# CanBus-8x-Schalter.net
KiCad netlist of a schematic drawn in EAGLE
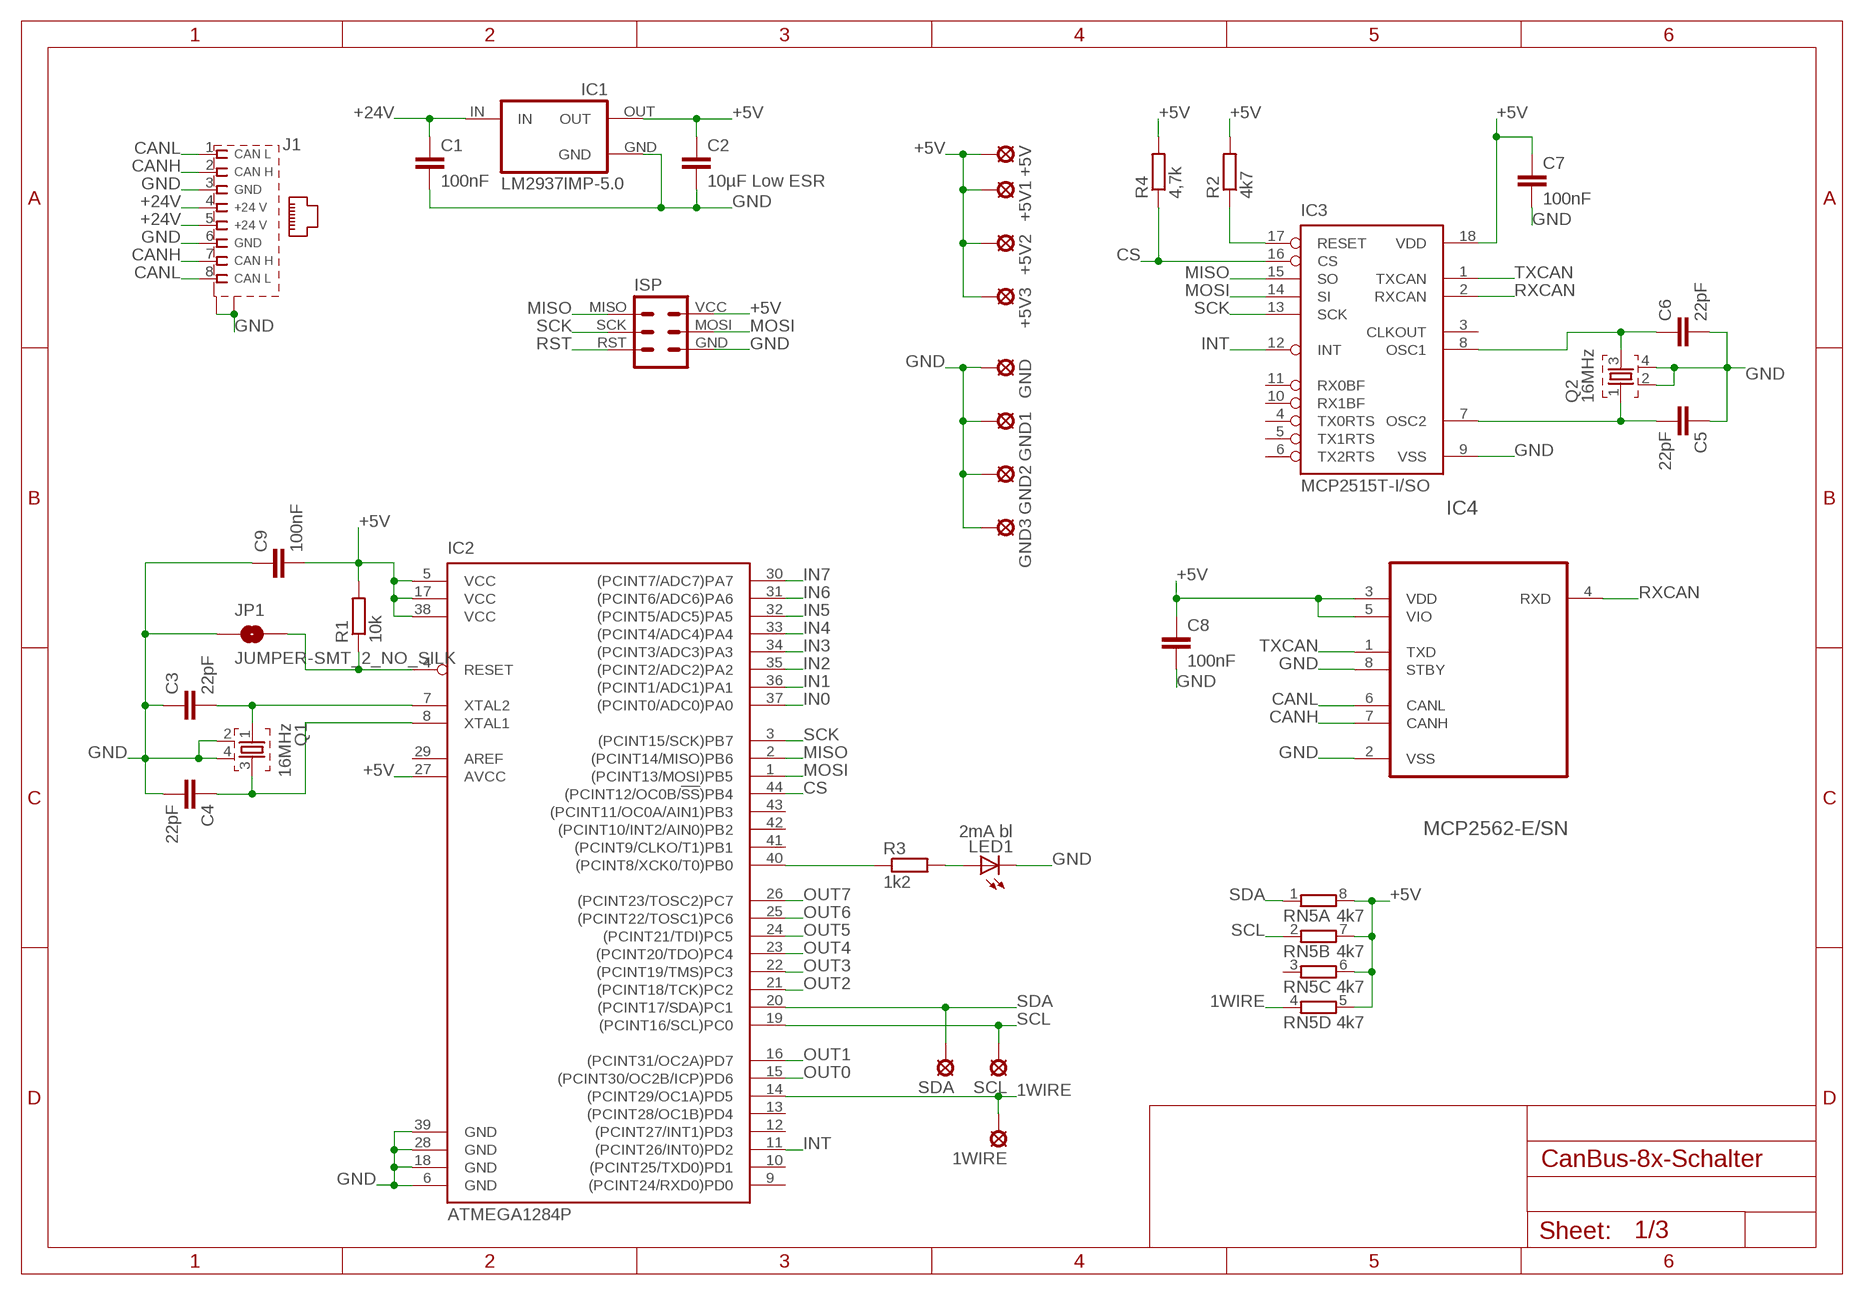
[diagram p0: schematic, sheet 1]
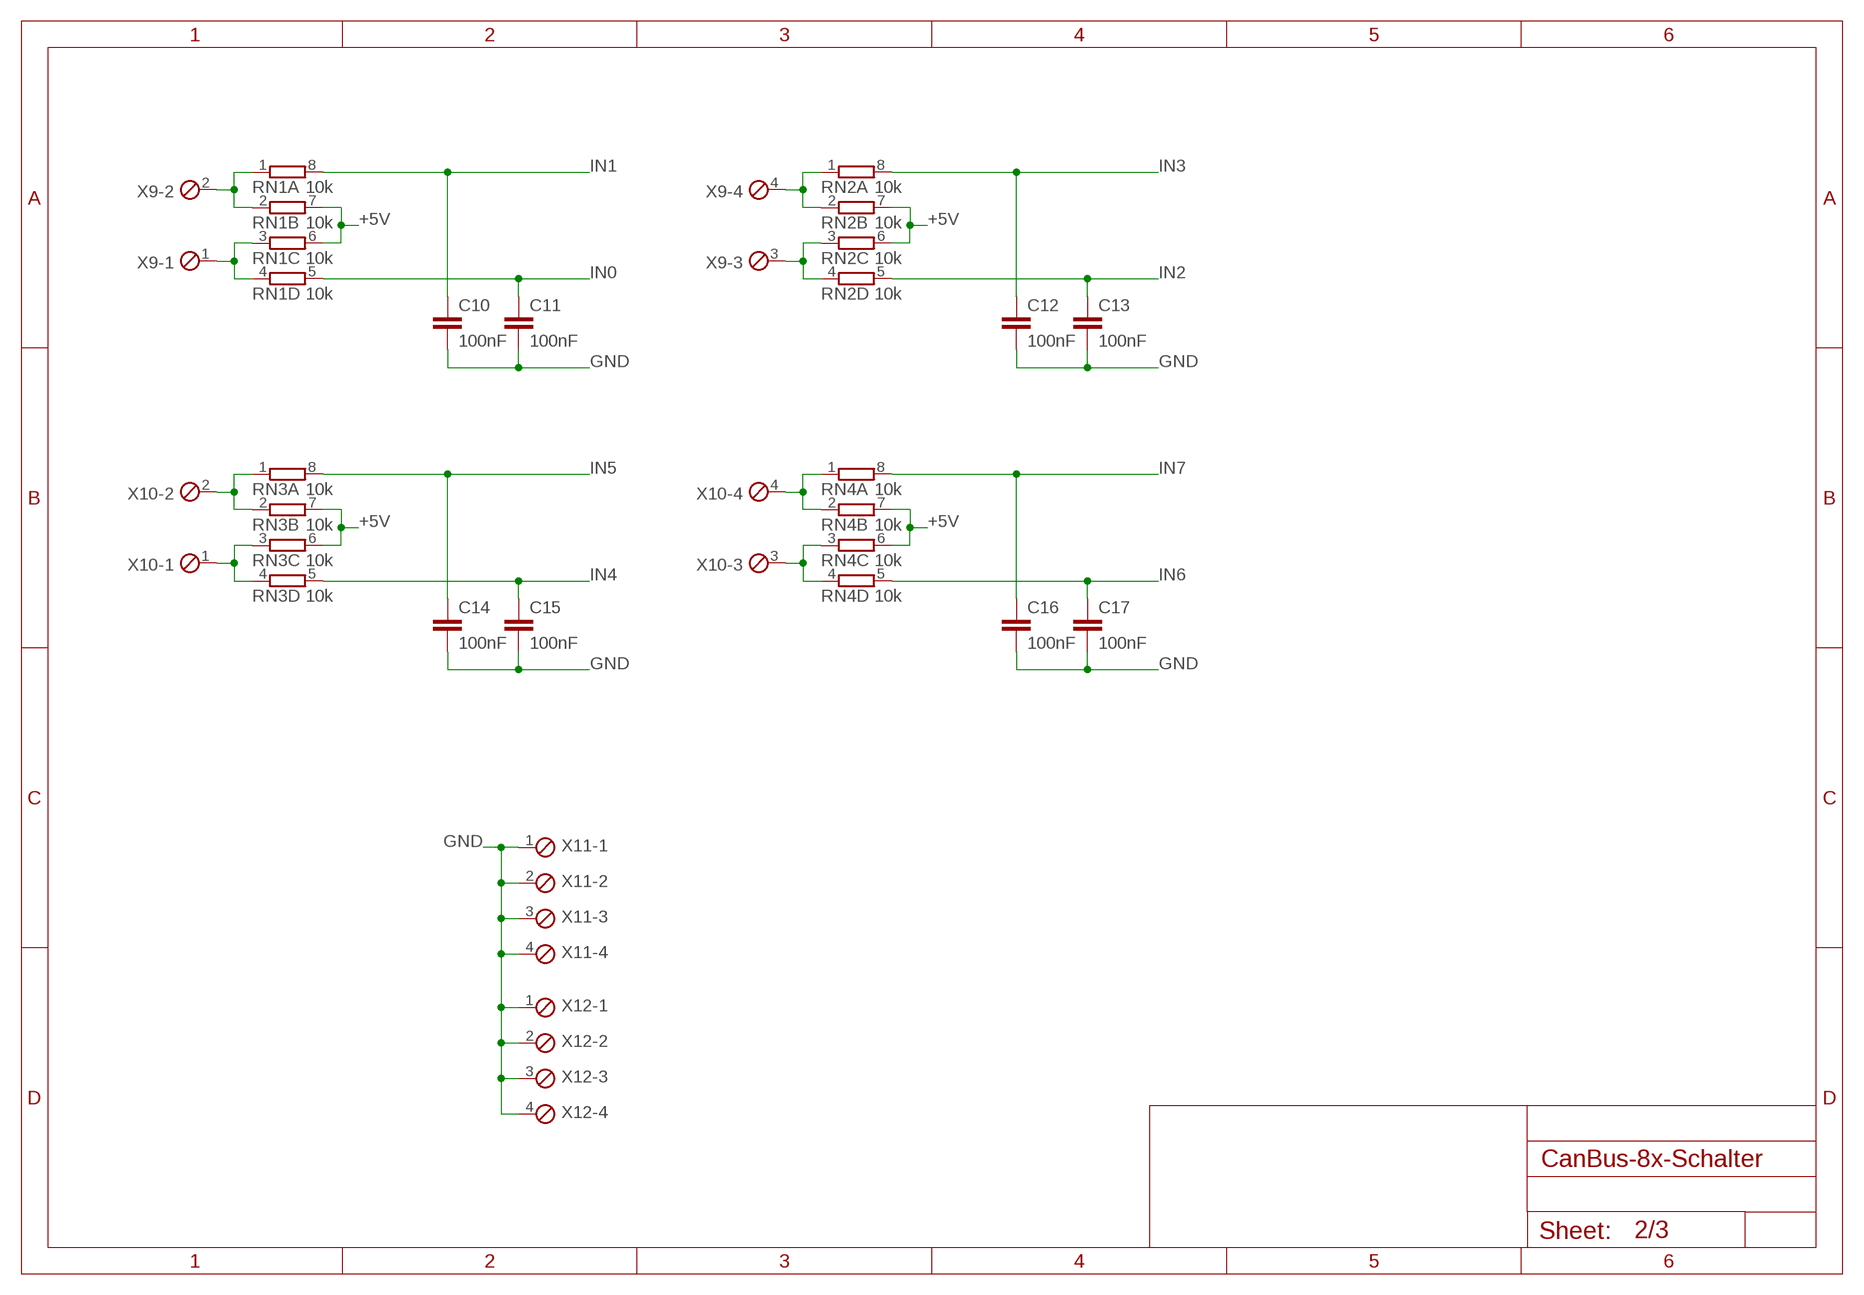
[diagram p1: schematic, sheet 2]
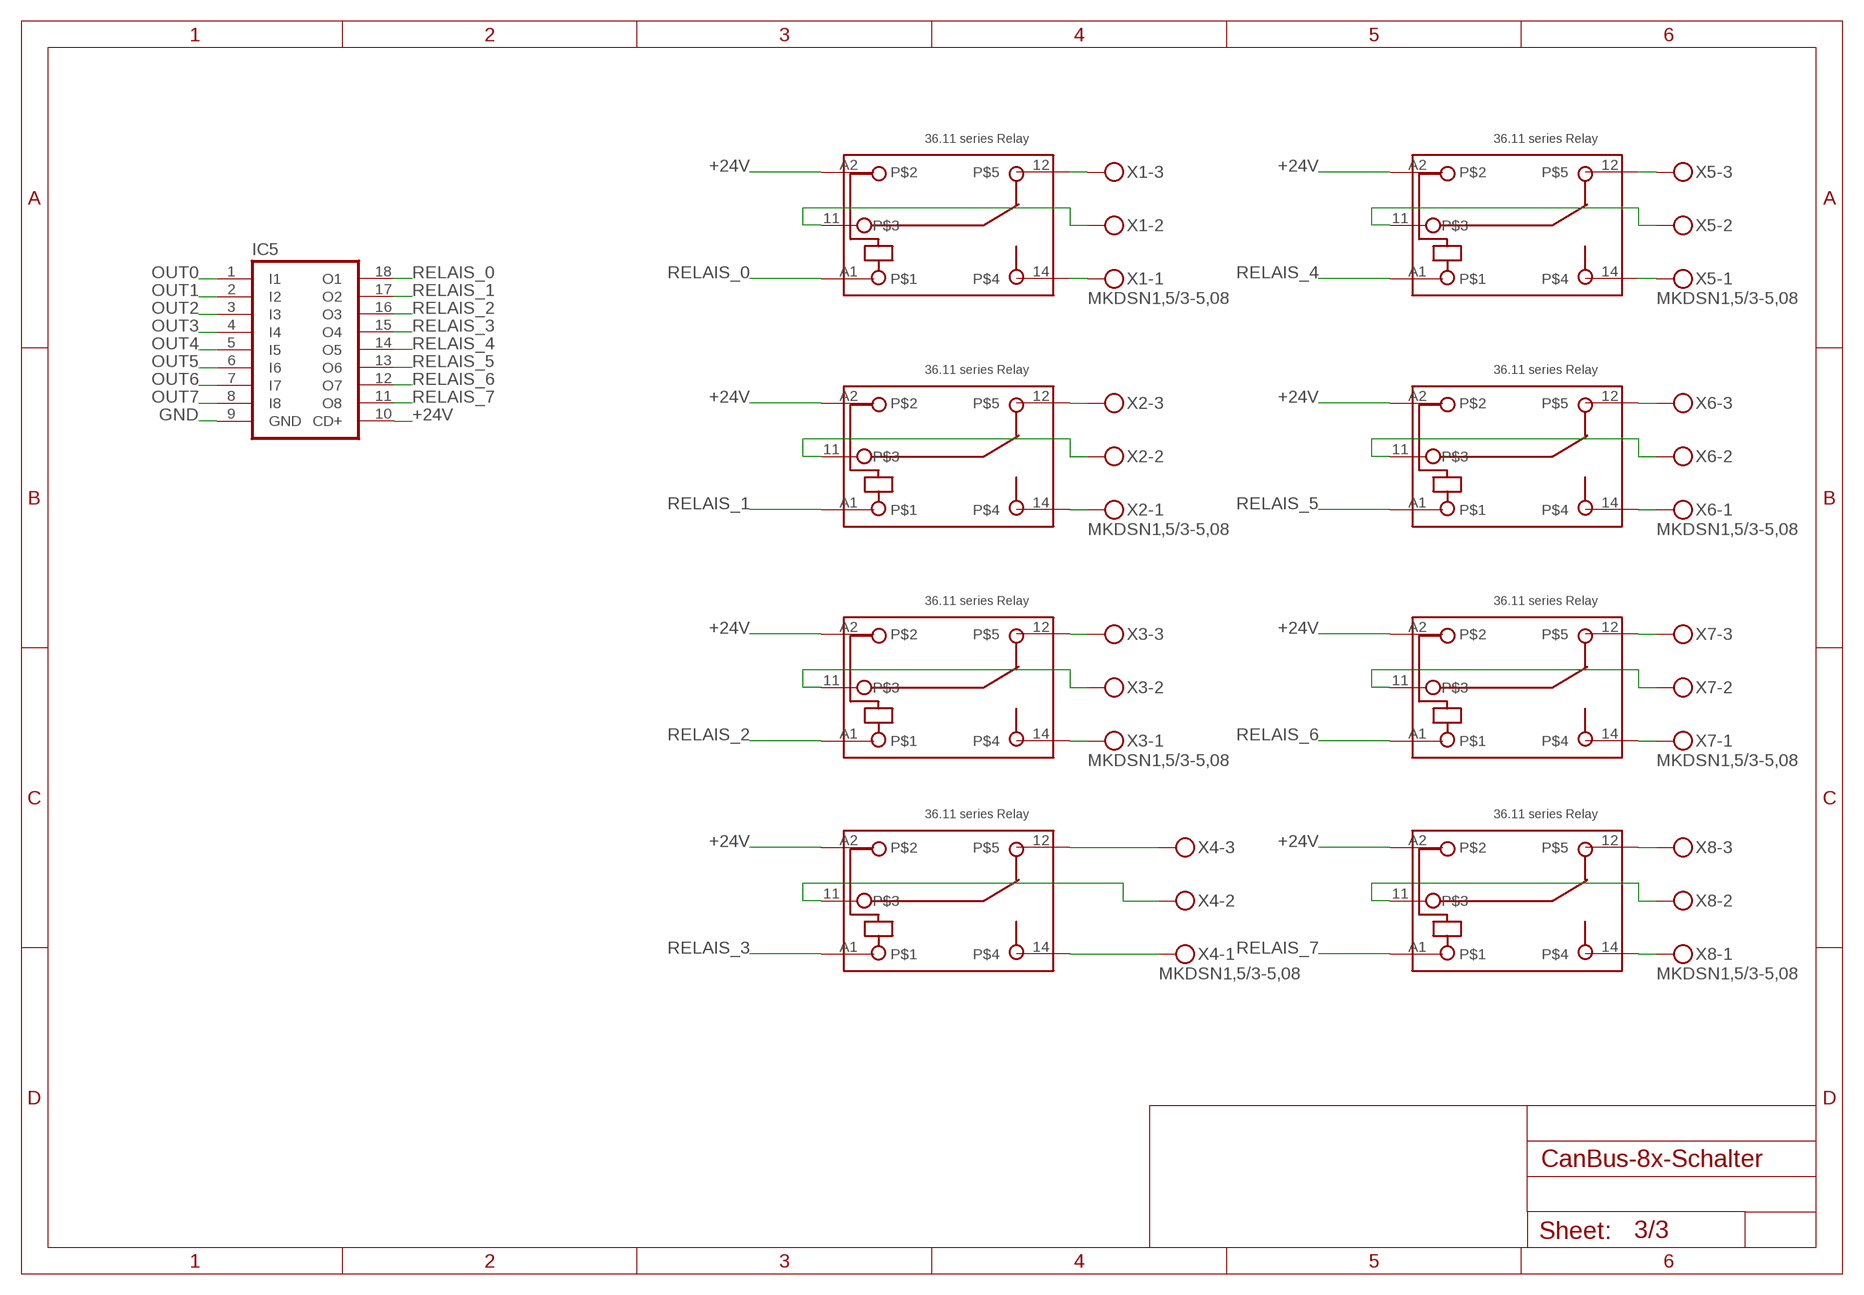
[diagram p2: schematic, sheet 3]

(export (version "E")
  (design (tool "Eeschema 10.0.6"))
  (components
    (comp (ref "C10")
      (value "100nF")
      (footprint "eagle-import:C0805")
      (libsource (lib "eagle-import") (part "C-EUC0805"))
    )
    (comp (ref "C11")
      (value "100nF")
      (footprint "eagle-import:C0805")
      (libsource (lib "eagle-import") (part "C-EUC0805"))
    )
    (comp (ref "C12")
      (value "100nF")
      (footprint "eagle-import:C0805")
      (libsource (lib "eagle-import") (part "C-EUC0805"))
    )
    (comp (ref "C13")
      (value "100nF")
      (footprint "eagle-import:C0805")
      (libsource (lib "eagle-import") (part "C-EUC0805"))
    )
    (comp (ref "C14")
      (value "100nF")
      (footprint "eagle-import:C0805")
      (libsource (lib "eagle-import") (part "C-EUC0805"))
    )
    (comp (ref "C15")
      (value "100nF")
      (footprint "eagle-import:C0805")
      (libsource (lib "eagle-import") (part "C-EUC0805"))
    )
    (comp (ref "C16")
      (value "100nF")
      (footprint "eagle-import:C0805")
      (libsource (lib "eagle-import") (part "C-EUC0805"))
    )
    (comp (ref "C17")
      (value "100nF")
      (footprint "eagle-import:C0805")
      (libsource (lib "eagle-import") (part "C-EUC0805"))
    )
    (comp (ref "RN1")
      (value "10k")
      (footprint "eagle-import:0603-ARC")
      (libsource (lib "eagle-import") (part "4R-N0603-ARC"))
    )
    (comp (ref "RN2")
      (value "10k")
      (footprint "eagle-import:0603-ARC")
      (libsource (lib "eagle-import") (part "4R-N0603-ARC"))
    )
    (comp (ref "RN3")
      (value "10k")
      (footprint "eagle-import:0603-ARC")
      (libsource (lib "eagle-import") (part "4R-N0603-ARC"))
    )
    (comp (ref "RN4")
      (value "10k")
      (footprint "eagle-import:0603-ARC")
      (libsource (lib "eagle-import") (part "4R-N0603-ARC"))
    )
    (comp (ref "X9")
      (value "MPT4")
      (footprint "eagle-import:4POL254")
      (libsource (lib "eagle-import") (part "MPT4"))
    )
    (comp (ref "X10")
      (value "MPT4")
      (footprint "eagle-import:4POL254")
      (libsource (lib "eagle-import") (part "MPT4"))
    )
    (comp (ref "X11")
      (value "MPT4")
      (footprint "eagle-import:4POL254")
      (libsource (lib "eagle-import") (part "MPT4"))
    )
    (comp (ref "X12")
      (value "MPT4")
      (footprint "eagle-import:4POL254")
      (libsource (lib "eagle-import") (part "MPT4"))
    )
    (comp (ref "IC5")
      (value "ULN2803A-SO18W")
      (footprint "eagle-import:SO18W")
      (libsource (lib "eagle-import") (part "ULN2803A-SO18W"))
    )
    (comp (ref "K1")
      (value "36.11")
      (footprint "eagle-import:36.11")
      (libsource (lib "eagle-import") (part "36.11"))
    )
    (comp (ref "K2")
      (value "36.11")
      (footprint "eagle-import:36.11")
      (libsource (lib "eagle-import") (part "36.11"))
    )
    (comp (ref "K3")
      (value "36.11")
      (footprint "eagle-import:36.11")
      (libsource (lib "eagle-import") (part "36.11"))
    )
    (comp (ref "K4")
      (value "36.11")
      (footprint "eagle-import:36.11")
      (libsource (lib "eagle-import") (part "36.11"))
    )
    (comp (ref "K5")
      (value "36.11")
      (footprint "eagle-import:36.11")
      (libsource (lib "eagle-import") (part "36.11"))
    )
    (comp (ref "K6")
      (value "36.11")
      (footprint "eagle-import:36.11")
      (libsource (lib "eagle-import") (part "36.11"))
    )
    (comp (ref "K7")
      (value "36.11")
      (footprint "eagle-import:36.11")
      (libsource (lib "eagle-import") (part "36.11"))
    )
    (comp (ref "K8")
      (value "36.11")
      (footprint "eagle-import:36.11")
      (libsource (lib "eagle-import") (part "36.11"))
    )
    (comp (ref "X1")
      (value "MKDSN1,5/3-5,08")
      (footprint "eagle-import:MKDSN1,5_3-5,08")
      (libsource (lib "eagle-import") (part "MKDSN1,5/3-5,08"))
    )
    (comp (ref "X2")
      (value "MKDSN1,5/3-5,08")
      (footprint "eagle-import:MKDSN1,5_3-5,08")
      (libsource (lib "eagle-import") (part "MKDSN1,5/3-5,08"))
    )
    (comp (ref "X3")
      (value "MKDSN1,5/3-5,08")
      (footprint "eagle-import:MKDSN1,5_3-5,08")
      (libsource (lib "eagle-import") (part "MKDSN1,5/3-5,08"))
    )
    (comp (ref "X4")
      (value "MKDSN1,5/3-5,08")
      (footprint "eagle-import:MKDSN1,5_3-5,08")
      (libsource (lib "eagle-import") (part "MKDSN1,5/3-5,08"))
    )
    (comp (ref "X5")
      (value "MKDSN1,5/3-5,08")
      (footprint "eagle-import:MKDSN1,5_3-5,08")
      (libsource (lib "eagle-import") (part "MKDSN1,5/3-5,08"))
    )
    (comp (ref "X6")
      (value "MKDSN1,5/3-5,08")
      (footprint "eagle-import:MKDSN1,5_3-5,08")
      (libsource (lib "eagle-import") (part "MKDSN1,5/3-5,08"))
    )
    (comp (ref "X7")
      (value "MKDSN1,5/3-5,08")
      (footprint "eagle-import:MKDSN1,5_3-5,08")
      (libsource (lib "eagle-import") (part "MKDSN1,5/3-5,08"))
    )
    (comp (ref "X8")
      (value "MKDSN1,5/3-5,08")
      (footprint "eagle-import:MKDSN1,5_3-5,08")
      (libsource (lib "eagle-import") (part "MKDSN1,5/3-5,08"))
    )
    (comp (ref "+5V")
      (value "LSP13")
      (footprint "eagle-import:LSP13")
      (libsource (lib "eagle-import") (part "LSP13"))
    )
    (comp (ref "+5V1")
      (value "LSP13")
      (footprint "eagle-import:LSP13")
      (libsource (lib "eagle-import") (part "LSP13"))
    )
    (comp (ref "+5V2")
      (value "LSP13")
      (footprint "eagle-import:LSP13")
      (libsource (lib "eagle-import") (part "LSP13"))
    )
    (comp (ref "+5V3")
      (value "LSP13")
      (footprint "eagle-import:LSP13")
      (libsource (lib "eagle-import") (part "LSP13"))
    )
    (comp (ref "1WIRE")
      (value "LSP13")
      (footprint "eagle-import:LSP13")
      (libsource (lib "eagle-import") (part "LSP13"))
    )
    (comp (ref "C1")
      (value "100nF")
      (footprint "eagle-import:C0805")
      (libsource (lib "eagle-import") (part "C-EUC0805"))
    )
    (comp (ref "C2")
      (value "10µF Low ESR")
      (footprint "eagle-import:C0805")
      (libsource (lib "eagle-import") (part "C-EUC0805"))
    )
    (comp (ref "C3")
      (value "22pF")
      (footprint "eagle-import:C0805")
      (libsource (lib "eagle-import") (part "C-EUC0805"))
    )
    (comp (ref "C4")
      (value "22pF")
      (footprint "eagle-import:C0805")
      (libsource (lib "eagle-import") (part "C-EUC0805"))
    )
    (comp (ref "C5")
      (value "22pF")
      (footprint "eagle-import:C0805")
      (libsource (lib "eagle-import") (part "C-EUC0805"))
    )
    (comp (ref "C6")
      (value "22pF")
      (footprint "eagle-import:C0805")
      (libsource (lib "eagle-import") (part "C-EUC0805"))
    )
    (comp (ref "C7")
      (value "100nF")
      (footprint "eagle-import:C0805")
      (libsource (lib "eagle-import") (part "C-EUC0805"))
    )
    (comp (ref "C8")
      (value "100nF")
      (footprint "eagle-import:C0805")
      (libsource (lib "eagle-import") (part "C-EUC0805"))
    )
    (comp (ref "C9")
      (value "100nF")
      (footprint "eagle-import:C0805")
      (libsource (lib "eagle-import") (part "C-EUC0805"))
    )
    (comp (ref "GND")
      (value "LSP13")
      (footprint "eagle-import:LSP13")
      (libsource (lib "eagle-import") (part "LSP13"))
    )
    (comp (ref "GND1")
      (value "LSP13")
      (footprint "eagle-import:LSP13")
      (libsource (lib "eagle-import") (part "LSP13"))
    )
    (comp (ref "GND2")
      (value "LSP13")
      (footprint "eagle-import:LSP13")
      (libsource (lib "eagle-import") (part "LSP13"))
    )
    (comp (ref "GND3")
      (value "LSP13")
      (footprint "eagle-import:LSP13")
      (libsource (lib "eagle-import") (part "LSP13"))
    )
    (comp (ref "IC1")
      (value "LM2937IMP-5.0")
      (footprint "eagle-import:SOT223")
      (libsource (lib "eagle-import") (part "LM2937IMP-5.0"))
    )
    (comp (ref "IC2")
      (value "ATMEGA1284P")
      (footprint "eagle-import:TQFP44")
      (fields (field (name "MPN") "ATMEGA644PV-10AU"))
      (libsource (lib "eagle-import") (part "ATMEGA644A"))
    )
    (comp (ref "IC3")
      (value "MCP2515T-I/SO")
      (footprint "eagle-import:SO18L")
      (libsource (lib "eagle-import") (part "MCP2515T-I/SO"))
    )
    (comp (ref "IC4")
      (value "MCP2562-E/SN")
      (footprint "eagle-import:SO08")
      (libsource (lib "eagle-import") (part "MCP2562-E/SN"))
    )
    (comp (ref "ISP")
      (value "ISPVIAS-ONLY-1.27MM")
      (footprint "eagle-import:ISP-VIAS-ONLY-1.27MM")
      (libsource (lib "eagle-import") (part "ISPVIAS-ONLY-1.27MM"))
    )
    (comp (ref "J1")
      (value "RJ45-CAN")
      (footprint "eagle-import:MEBP_8-8G")
      (libsource (lib "eagle-import") (part "RJ45-CAN"))
    )
    (comp (ref "JP1")
      (value "JUMPER-SMT_2_NO_SILK")
      (footprint "eagle-import:SMT-JUMPER_2_NO_SILK")
      (libsource (lib "eagle-import") (part "JUMPER-SMT_2_NO_SILK"))
    )
    (comp (ref "LED1")
      (value "2mA bl")
      (footprint "eagle-import:CHIPLED_1206")
      (libsource (lib "eagle-import") (part "LEDCHIPLED_1206"))
    )
    (comp (ref "Q1")
      (value "16MHz")
      (footprint "eagle-import:MJ-5X3.2")
      (libsource (lib "eagle-import") (part "EUROQUARTZ-MMJ"))
    )
    (comp (ref "Q2")
      (value "16MHz")
      (footprint "eagle-import:MJ-5X3.2")
      (libsource (lib "eagle-import") (part "EUROQUARTZ-MMJ"))
    )
    (comp (ref "R1")
      (value "10k")
      (footprint "eagle-import:R0805")
      (libsource (lib "eagle-import") (part "R-EU_R0805"))
    )
    (comp (ref "R2")
      (value "4k7")
      (footprint "eagle-import:R0805")
      (libsource (lib "eagle-import") (part "R-EU_R0805"))
    )
    (comp (ref "R3")
      (value "1k2")
      (footprint "eagle-import:R0805")
      (libsource (lib "eagle-import") (part "R-EU_R0805"))
    )
    (comp (ref "R4")
      (value "4,7k")
      (footprint "eagle-import:R0805")
      (libsource (lib "eagle-import") (part "R-EU_R0805"))
    )
    (comp (ref "RN5")
      (value "4k7")
      (footprint "eagle-import:0603-ARC")
      (libsource (lib "eagle-import") (part "4R-N0603-ARC"))
    )
    (comp (ref "SCL")
      (value "LSP13")
      (footprint "eagle-import:LSP13")
      (libsource (lib "eagle-import") (part "LSP13"))
    )
    (comp (ref "SDA")
      (value "LSP13")
      (footprint "eagle-import:LSP13")
      (libsource (lib "eagle-import") (part "LSP13"))
    )
  )
  (nets
    (net (code "1") (name "+5V") (class "Default")
      (node (ref "+5V") (pin "MP") (pinfunction "MP_MP") (pintype "passive"))
      (node (ref "+5V1") (pin "MP") (pinfunction "MP_MP") (pintype "passive"))
      (node (ref "+5V2") (pin "MP") (pinfunction "MP_MP") (pintype "passive"))
      (node (ref "+5V3") (pin "MP") (pinfunction "MP_MP") (pintype "passive"))
      (node (ref "C2") (pin "1") (pinfunction "1_1") (pintype "passive"))
      (node (ref "C7") (pin "1") (pinfunction "1_1") (pintype "passive"))
      (node (ref "C8") (pin "1") (pinfunction "1_1") (pintype "passive"))
      (node (ref "C9") (pin "2") (pinfunction "2_2") (pintype "passive"))
      (node (ref "IC1") (pin "OUT") (pinfunction "OUT_OUT") (pintype "output"))
      (node (ref "IC2") (pin "17") (pinfunction "VCC_17") (pintype "power_in"))
      (node (ref "IC2") (pin "27") (pinfunction "AVCC_27") (pintype "power_in"))
      (node (ref "IC2") (pin "38") (pinfunction "VCC_38") (pintype "power_in"))
      (node (ref "IC2") (pin "5") (pinfunction "VCC_5") (pintype "power_in"))
      (node (ref "IC3") (pin "18") (pinfunction "VDD_18") (pintype "power_in"))
      (node (ref "IC4") (pin "3") (pinfunction "VDD_3") (pintype "power_in"))
      (node (ref "IC4") (pin "5") (pinfunction "VIO_5") (pintype "power_in"))
      (node (ref "ISP") (pin "VCC") (pinfunction "VCC_VCC") (pintype "passive"))
      (node (ref "R1") (pin "2") (pinfunction "2_2") (pintype "passive"))
      (node (ref "R2") (pin "2") (pinfunction "2_2") (pintype "passive"))
      (node (ref "R4") (pin "2") (pinfunction "2_2") (pintype "passive"))
      (node (ref "RN1") (pin "6") (pinfunction "2_6") (pintype "passive"))
      (node (ref "RN1") (pin "7") (pinfunction "2_7") (pintype "passive"))
      (node (ref "RN2") (pin "6") (pinfunction "2_6") (pintype "passive"))
      (node (ref "RN2") (pin "7") (pinfunction "2_7") (pintype "passive"))
      (node (ref "RN3") (pin "6") (pinfunction "2_6") (pintype "passive"))
      (node (ref "RN3") (pin "7") (pinfunction "2_7") (pintype "passive"))
      (node (ref "RN4") (pin "6") (pinfunction "2_6") (pintype "passive"))
      (node (ref "RN4") (pin "7") (pinfunction "2_7") (pintype "passive"))
      (node (ref "RN5") (pin "5") (pinfunction "2_5") (pintype "passive"))
      (node (ref "RN5") (pin "6") (pinfunction "2_6") (pintype "passive"))
      (node (ref "RN5") (pin "7") (pinfunction "2_7") (pintype "passive"))
      (node (ref "RN5") (pin "8") (pinfunction "2_8") (pintype "passive"))
    )
    (net (code "2") (name "+24V") (class "Default")
      (node (ref "C1") (pin "1") (pinfunction "1_1") (pintype "passive"))
      (node (ref "IC1") (pin "IN") (pinfunction "IN_IN") (pintype "input"))
      (node (ref "IC5") (pin "10") (pinfunction "CD+_10") (pintype "passive"))
      (node (ref "J1") (pin "4") (pinfunction "4_4") (pintype "passive"))
      (node (ref "J1") (pin "5") (pinfunction "5_5") (pintype "passive"))
      (node (ref "K1") (pin "A2") (pinfunction "P$2_A2") (pintype "passive"))
      (node (ref "K2") (pin "A2") (pinfunction "P$2_A2") (pintype "passive"))
      (node (ref "K3") (pin "A2") (pinfunction "P$2_A2") (pintype "passive"))
      (node (ref "K4") (pin "A2") (pinfunction "P$2_A2") (pintype "passive"))
      (node (ref "K5") (pin "A2") (pinfunction "P$2_A2") (pintype "passive"))
      (node (ref "K6") (pin "A2") (pinfunction "P$2_A2") (pintype "passive"))
      (node (ref "K7") (pin "A2") (pinfunction "P$2_A2") (pintype "passive"))
      (node (ref "K8") (pin "A2") (pinfunction "P$2_A2") (pintype "passive"))
    )
    (net (code "3") (name "1WIRE") (class "Default")
      (node (ref "1WIRE") (pin "MP") (pinfunction "MP_MP") (pintype "passive"))
      (node (ref "IC2") (pin "14") (pinfunction "(PCINT29/OC1A)PD5_14") (pintype "bidirectional"))
      (node (ref "RN5") (pin "4") (pinfunction "1_4") (pintype "passive"))
    )
    (net (code "4") (name "CANH") (class "Default")
      (node (ref "IC4") (pin "7") (pinfunction "CANH_7") (pintype "bidirectional"))
      (node (ref "J1") (pin "2") (pinfunction "2_2") (pintype "passive"))
      (node (ref "J1") (pin "7") (pinfunction "7_7") (pintype "passive"))
    )
    (net (code "5") (name "CANL") (class "Default")
      (node (ref "IC4") (pin "6") (pinfunction "CANL_6") (pintype "bidirectional"))
      (node (ref "J1") (pin "1") (pinfunction "1_1") (pintype "passive"))
      (node (ref "J1") (pin "8") (pinfunction "8_8") (pintype "passive"))
    )
    (net (code "6") (name "CS") (class "Default")
      (node (ref "IC2") (pin "44") (pinfunction "(PCINT12/OC0B/~{SS})PB4_44") (pintype "bidirectional"))
      (node (ref "IC3") (pin "16") (pinfunction "CS_16") (pintype "input"))
      (node (ref "R4") (pin "1") (pinfunction "1_1") (pintype "passive"))
    )
    (net (code "7") (name "GND") (class "Default")
      (node (ref "C1") (pin "2") (pinfunction "2_2") (pintype "passive"))
      (node (ref "C10") (pin "2") (pinfunction "2_2") (pintype "passive"))
      (node (ref "C11") (pin "2") (pinfunction "2_2") (pintype "passive"))
      (node (ref "C12") (pin "2") (pinfunction "2_2") (pintype "passive"))
      (node (ref "C13") (pin "2") (pinfunction "2_2") (pintype "passive"))
      (node (ref "C14") (pin "2") (pinfunction "2_2") (pintype "passive"))
      (node (ref "C15") (pin "2") (pinfunction "2_2") (pintype "passive"))
      (node (ref "C16") (pin "2") (pinfunction "2_2") (pintype "passive"))
      (node (ref "C17") (pin "2") (pinfunction "2_2") (pintype "passive"))
      (node (ref "C2") (pin "2") (pinfunction "2_2") (pintype "passive"))
      (node (ref "C3") (pin "1") (pinfunction "1_1") (pintype "passive"))
      (node (ref "C4") (pin "2") (pinfunction "2_2") (pintype "passive"))
      (node (ref "C5") (pin "1") (pinfunction "1_1") (pintype "passive"))
      (node (ref "C6") (pin "2") (pinfunction "2_2") (pintype "passive"))
      (node (ref "C7") (pin "2") (pinfunction "2_2") (pintype "passive"))
      (node (ref "C8") (pin "2") (pinfunction "2_2") (pintype "passive"))
      (node (ref "C9") (pin "1") (pinfunction "1_1") (pintype "passive"))
      (node (ref "GND") (pin "MP") (pinfunction "MP_MP") (pintype "passive"))
      (node (ref "GND1") (pin "MP") (pinfunction "MP_MP") (pintype "passive"))
      (node (ref "GND2") (pin "MP") (pinfunction "MP_MP") (pintype "passive"))
      (node (ref "GND3") (pin "MP") (pinfunction "MP_MP") (pintype "passive"))
      (node (ref "IC1") (pin "GND") (pinfunction "GND_GND") (pintype "power_in"))
      (node (ref "IC2") (pin "18") (pinfunction "GND_18") (pintype "power_in"))
      (node (ref "IC2") (pin "28") (pinfunction "GND_28") (pintype "power_in"))
      (node (ref "IC2") (pin "39") (pinfunction "GND_39") (pintype "power_in"))
      (node (ref "IC2") (pin "6") (pinfunction "GND_6") (pintype "power_in"))
      (node (ref "IC3") (pin "9") (pinfunction "VSS_9") (pintype "power_in"))
      (node (ref "IC4") (pin "2") (pinfunction "VSS_2") (pintype "power_in"))
      (node (ref "IC4") (pin "8") (pinfunction "STBY_8") (pintype "input"))
      (node (ref "IC5") (pin "9") (pinfunction "GND_9") (pintype "power_in"))
      (node (ref "ISP") (pin "GND") (pinfunction "GND_GND") (pintype "passive"))
      (node (ref "J1") (pin "3") (pinfunction "3_3") (pintype "passive"))
      (node (ref "J1") (pin "6") (pinfunction "6_6") (pintype "passive"))
      (node (ref "J1") (pin "G1") (pinfunction "S1_G1") (pintype "passive"))
      (node (ref "J1") (pin "G2") (pinfunction "S2_G2") (pintype "passive"))
      (node (ref "JP1") (pin "1") (pinfunction "1_1") (pintype "passive"))
      (node (ref "LED1") (pin "C") (pinfunction "C_C") (pintype "passive"))
      (node (ref "Q1") (pin "2") (pinfunction "2_2") (pintype "passive"))
      (node (ref "Q1") (pin "4") (pinfunction "4_4") (pintype "passive"))
      (node (ref "Q2") (pin "2") (pinfunction "2_2") (pintype "passive"))
      (node (ref "Q2") (pin "4") (pinfunction "4_4") (pintype "passive"))
      (node (ref "X11") (pin "1") (pinfunction "1_1") (pintype "passive"))
      (node (ref "X11") (pin "2") (pinfunction "1_2") (pintype "passive"))
      (node (ref "X11") (pin "3") (pinfunction "1_3") (pintype "passive"))
      (node (ref "X11") (pin "4") (pinfunction "1_4") (pintype "passive"))
      (node (ref "X12") (pin "1") (pinfunction "1_1") (pintype "passive"))
      (node (ref "X12") (pin "2") (pinfunction "1_2") (pintype "passive"))
      (node (ref "X12") (pin "3") (pinfunction "1_3") (pintype "passive"))
      (node (ref "X12") (pin "4") (pinfunction "1_4") (pintype "passive"))
    )
    (net (code "8") (name "IN0") (class "Default")
      (node (ref "C11") (pin "1") (pinfunction "1_1") (pintype "passive"))
      (node (ref "IC2") (pin "37") (pinfunction "(PCINT0/ADC0)PA0_37") (pintype "bidirectional"))
      (node (ref "RN1") (pin "5") (pinfunction "2_5") (pintype "passive"))
    )
    (net (code "9") (name "IN1") (class "Default")
      (node (ref "C10") (pin "1") (pinfunction "1_1") (pintype "passive"))
      (node (ref "IC2") (pin "36") (pinfunction "(PCINT1/ADC1)PA1_36") (pintype "bidirectional"))
      (node (ref "RN1") (pin "8") (pinfunction "2_8") (pintype "passive"))
    )
    (net (code "10") (name "IN2") (class "Default")
      (node (ref "C13") (pin "1") (pinfunction "1_1") (pintype "passive"))
      (node (ref "IC2") (pin "35") (pinfunction "(PCINT2/ADC2)PA2_35") (pintype "bidirectional"))
      (node (ref "RN2") (pin "5") (pinfunction "2_5") (pintype "passive"))
    )
    (net (code "11") (name "IN3") (class "Default")
      (node (ref "C12") (pin "1") (pinfunction "1_1") (pintype "passive"))
      (node (ref "IC2") (pin "34") (pinfunction "(PCINT3/ADC3)PA3_34") (pintype "bidirectional"))
      (node (ref "RN2") (pin "8") (pinfunction "2_8") (pintype "passive"))
    )
    (net (code "12") (name "IN4") (class "Default")
      (node (ref "C15") (pin "1") (pinfunction "1_1") (pintype "passive"))
      (node (ref "IC2") (pin "33") (pinfunction "(PCINT4/ADC4)PA4_33") (pintype "bidirectional"))
      (node (ref "RN3") (pin "5") (pinfunction "2_5") (pintype "passive"))
    )
    (net (code "13") (name "IN5") (class "Default")
      (node (ref "C14") (pin "1") (pinfunction "1_1") (pintype "passive"))
      (node (ref "IC2") (pin "32") (pinfunction "(PCINT5/ADC5)PA5_32") (pintype "bidirectional"))
      (node (ref "RN3") (pin "8") (pinfunction "2_8") (pintype "passive"))
    )
    (net (code "14") (name "IN6") (class "Default")
      (node (ref "C17") (pin "1") (pinfunction "1_1") (pintype "passive"))
      (node (ref "IC2") (pin "31") (pinfunction "(PCINT6/ADC6)PA6_31") (pintype "bidirectional"))
      (node (ref "RN4") (pin "5") (pinfunction "2_5") (pintype "passive"))
    )
    (net (code "15") (name "IN7") (class "Default")
      (node (ref "C16") (pin "1") (pinfunction "1_1") (pintype "passive"))
      (node (ref "IC2") (pin "30") (pinfunction "(PCINT7/ADC7)PA7_30") (pintype "bidirectional"))
      (node (ref "RN4") (pin "8") (pinfunction "2_8") (pintype "passive"))
    )
    (net (code "16") (name "INT") (class "Default")
      (node (ref "IC2") (pin "11") (pinfunction "(PCINT26/INT0)PD2_11") (pintype "bidirectional"))
      (node (ref "IC3") (pin "12") (pinfunction "INT_12") (pintype "output"))
    )
    (net (code "17") (name "MISO") (class "Default")
      (node (ref "IC2") (pin "2") (pinfunction "(PCINT14/MISO)PB6_2") (pintype "bidirectional"))
      (node (ref "IC3") (pin "15") (pinfunction "SO_15") (pintype "output"))
      (node (ref "ISP") (pin "MISO") (pinfunction "MISO_MISO") (pintype "passive"))
    )
    (net (code "18") (name "MOSI") (class "Default")
      (node (ref "IC2") (pin "1") (pinfunction "(PCINT13/MOSI)PB5_1") (pintype "bidirectional"))
      (node (ref "IC3") (pin "14") (pinfunction "SI_14") (pintype "input"))
      (node (ref "ISP") (pin "MOSI") (pinfunction "MOSI_MOSI") (pintype "passive"))
    )
    (net (code "19") (name "Net-(IC2-(PCINT8{slash}XCK0{slash}T0)PB0)") (class "Default")
      (node (ref "IC2") (pin "40") (pinfunction "(PCINT8/XCK0/T0)PB0_40") (pintype "bidirectional"))
      (node (ref "R3") (pin "1") (pinfunction "1_1") (pintype "passive"))
    )
    (net (code "20") (name "Net-(IC2-XTAL1)") (class "Default")
      (node (ref "C4") (pin "1") (pinfunction "1_1") (pintype "passive"))
      (node (ref "IC2") (pin "8") (pinfunction "XTAL1_8") (pintype "bidirectional"))
      (node (ref "Q1") (pin "3") (pinfunction "3_3") (pintype "passive"))
    )
    (net (code "21") (name "Net-(IC2-XTAL2)") (class "Default")
      (node (ref "C3") (pin "2") (pinfunction "2_2") (pintype "passive"))
      (node (ref "IC2") (pin "7") (pinfunction "XTAL2_7") (pintype "bidirectional"))
      (node (ref "Q1") (pin "1") (pinfunction "1_1") (pintype "passive"))
    )
    (net (code "22") (name "Net-(IC3-OSC1)") (class "Default")
      (node (ref "C6") (pin "1") (pinfunction "1_1") (pintype "passive"))
      (node (ref "IC3") (pin "8") (pinfunction "OSC1_8") (pintype "input"))
      (node (ref "Q2") (pin "3") (pinfunction "3_3") (pintype "passive"))
    )
    (net (code "23") (name "Net-(IC3-OSC2)") (class "Default")
      (node (ref "C5") (pin "2") (pinfunction "2_2") (pintype "passive"))
      (node (ref "IC3") (pin "7") (pinfunction "OSC2_7") (pintype "output"))
      (node (ref "Q2") (pin "1") (pinfunction "1_1") (pintype "passive"))
    )
    (net (code "24") (name "Net-(IC3-RESET)") (class "Default")
      (node (ref "IC3") (pin "17") (pinfunction "RESET_17") (pintype "input"))
      (node (ref "R2") (pin "1") (pinfunction "1_1") (pintype "passive"))
    )
    (net (code "25") (name "Net-(K1-P$3)") (class "Default")
      (node (ref "K1") (pin "11") (pinfunction "P$3_11") (pintype "passive"))
      (node (ref "X1") (pin "2") (pinfunction "KL_2") (pintype "passive"))
    )
    (net (code "26") (name "Net-(K1-P$4)") (class "Default")
      (node (ref "K1") (pin "14") (pinfunction "P$4_14") (pintype "passive"))
      (node (ref "X1") (pin "1") (pinfunction "KL_1") (pintype "passive"))
    )
    (net (code "27") (name "Net-(K1-P$5)") (class "Default")
      (node (ref "K1") (pin "12") (pinfunction "P$5_12") (pintype "passive"))
      (node (ref "X1") (pin "3") (pinfunction "KL_3") (pintype "passive"))
    )
    (net (code "28") (name "Net-(K2-P$3)") (class "Default")
      (node (ref "K2") (pin "11") (pinfunction "P$3_11") (pintype "passive"))
      (node (ref "X2") (pin "2") (pinfunction "KL_2") (pintype "passive"))
    )
    (net (code "29") (name "Net-(K2-P$4)") (class "Default")
      (node (ref "K2") (pin "14") (pinfunction "P$4_14") (pintype "passive"))
      (node (ref "X2") (pin "1") (pinfunction "KL_1") (pintype "passive"))
    )
    (net (code "30") (name "Net-(K2-P$5)") (class "Default")
      (node (ref "K2") (pin "12") (pinfunction "P$5_12") (pintype "passive"))
      (node (ref "X2") (pin "3") (pinfunction "KL_3") (pintype "passive"))
    )
    (net (code "31") (name "Net-(K3-P$3)") (class "Default")
      (node (ref "K3") (pin "11") (pinfunction "P$3_11") (pintype "passive"))
      (node (ref "X3") (pin "2") (pinfunction "KL_2") (pintype "passive"))
    )
    (net (code "32") (name "Net-(K3-P$4)") (class "Default")
      (node (ref "K3") (pin "14") (pinfunction "P$4_14") (pintype "passive"))
      (node (ref "X3") (pin "1") (pinfunction "KL_1") (pintype "passive"))
    )
    (net (code "33") (name "Net-(K3-P$5)") (class "Default")
      (node (ref "K3") (pin "12") (pinfunction "P$5_12") (pintype "passive"))
      (node (ref "X3") (pin "3") (pinfunction "KL_3") (pintype "passive"))
    )
    (net (code "34") (name "Net-(K4-P$3)") (class "Default")
      (node (ref "K4") (pin "11") (pinfunction "P$3_11") (pintype "passive"))
      (node (ref "X4") (pin "2") (pinfunction "KL_2") (pintype "passive"))
    )
    (net (code "35") (name "Net-(K4-P$4)") (class "Default")
      (node (ref "K4") (pin "14") (pinfunction "P$4_14") (pintype "passive"))
      (node (ref "X4") (pin "1") (pinfunction "KL_1") (pintype "passive"))
    )
    (net (code "36") (name "Net-(K4-P$5)") (class "Default")
      (node (ref "K4") (pin "12") (pinfunction "P$5_12") (pintype "passive"))
      (node (ref "X4") (pin "3") (pinfunction "KL_3") (pintype "passive"))
    )
    (net (code "37") (name "Net-(K5-P$3)") (class "Default")
      (node (ref "K5") (pin "11") (pinfunction "P$3_11") (pintype "passive"))
      (node (ref "X5") (pin "2") (pinfunction "KL_2") (pintype "passive"))
    )
    (net (code "38") (name "Net-(K5-P$4)") (class "Default")
      (node (ref "K5") (pin "14") (pinfunction "P$4_14") (pintype "passive"))
      (node (ref "X5") (pin "1") (pinfunction "KL_1") (pintype "passive"))
    )
    (net (code "39") (name "Net-(K5-P$5)") (class "Default")
      (node (ref "K5") (pin "12") (pinfunction "P$5_12") (pintype "passive"))
      (node (ref "X5") (pin "3") (pinfunction "KL_3") (pintype "passive"))
    )
    (net (code "40") (name "Net-(K6-P$3)") (class "Default")
      (node (ref "K6") (pin "11") (pinfunction "P$3_11") (pintype "passive"))
      (node (ref "X6") (pin "2") (pinfunction "KL_2") (pintype "passive"))
    )
    (net (code "41") (name "Net-(K6-P$4)") (class "Default")
      (node (ref "K6") (pin "14") (pinfunction "P$4_14") (pintype "passive"))
      (node (ref "X6") (pin "1") (pinfunction "KL_1") (pintype "passive"))
    )
    (net (code "42") (name "Net-(K6-P$5)") (class "Default")
      (node (ref "K6") (pin "12") (pinfunction "P$5_12") (pintype "passive"))
      (node (ref "X6") (pin "3") (pinfunction "KL_3") (pintype "passive"))
    )
    (net (code "43") (name "Net-(K7-P$3)") (class "Default")
      (node (ref "K7") (pin "11") (pinfunction "P$3_11") (pintype "passive"))
      (node (ref "X7") (pin "2") (pinfunction "KL_2") (pintype "passive"))
    )
    (net (code "44") (name "Net-(K7-P$4)") (class "Default")
      (node (ref "K7") (pin "14") (pinfunction "P$4_14") (pintype "passive"))
      (node (ref "X7") (pin "1") (pinfunction "KL_1") (pintype "passive"))
    )
    (net (code "45") (name "Net-(K7-P$5)") (class "Default")
      (node (ref "K7") (pin "12") (pinfunction "P$5_12") (pintype "passive"))
      (node (ref "X7") (pin "3") (pinfunction "KL_3") (pintype "passive"))
    )
    (net (code "46") (name "Net-(K8-P$3)") (class "Default")
      (node (ref "K8") (pin "11") (pinfunction "P$3_11") (pintype "passive"))
      (node (ref "X8") (pin "2") (pinfunction "KL_2") (pintype "passive"))
    )
    (net (code "47") (name "Net-(K8-P$4)") (class "Default")
      (node (ref "K8") (pin "14") (pinfunction "P$4_14") (pintype "passive"))
      (node (ref "X8") (pin "1") (pinfunction "KL_1") (pintype "passive"))
    )
    (net (code "48") (name "Net-(K8-P$5)") (class "Default")
      (node (ref "K8") (pin "12") (pinfunction "P$5_12") (pintype "passive"))
      (node (ref "X8") (pin "3") (pinfunction "KL_3") (pintype "passive"))
    )
    (net (code "49") (name "Net-(LED1-PadA)") (class "Default")
      (node (ref "LED1") (pin "A") (pinfunction "A_A") (pintype "passive"))
      (node (ref "R3") (pin "2") (pinfunction "2_2") (pintype "passive"))
    )
    (net (code "50") (name "Net-(RN1B-1)") (class "Default")
      (node (ref "RN1") (pin "1") (pinfunction "1_1") (pintype "passive"))
      (node (ref "RN1") (pin "2") (pinfunction "1_2") (pintype "passive"))
      (node (ref "X9") (pin "2") (pinfunction "1_2") (pintype "passive"))
    )
    (net (code "51") (name "Net-(RN1C-1)") (class "Default")
      (node (ref "RN1") (pin "3") (pinfunction "1_3") (pintype "passive"))
      (node (ref "RN1") (pin "4") (pinfunction "1_4") (pintype "passive"))
      (node (ref "X9") (pin "1") (pinfunction "1_1") (pintype "passive"))
    )
    (net (code "52") (name "Net-(RN2B-1)") (class "Default")
      (node (ref "RN2") (pin "1") (pinfunction "1_1") (pintype "passive"))
      (node (ref "RN2") (pin "2") (pinfunction "1_2") (pintype "passive"))
      (node (ref "X9") (pin "4") (pinfunction "1_4") (pintype "passive"))
    )
    (net (code "53") (name "Net-(RN2C-1)") (class "Default")
      (node (ref "RN2") (pin "3") (pinfunction "1_3") (pintype "passive"))
      (node (ref "RN2") (pin "4") (pinfunction "1_4") (pintype "passive"))
      (node (ref "X9") (pin "3") (pinfunction "1_3") (pintype "passive"))
    )
    (net (code "54") (name "Net-(RN3B-1)") (class "Default")
      (node (ref "RN3") (pin "1") (pinfunction "1_1") (pintype "passive"))
      (node (ref "RN3") (pin "2") (pinfunction "1_2") (pintype "passive"))
      (node (ref "X10") (pin "2") (pinfunction "1_2") (pintype "passive"))
    )
    (net (code "55") (name "Net-(RN3C-1)") (class "Default")
      (node (ref "RN3") (pin "3") (pinfunction "1_3") (pintype "passive"))
      (node (ref "RN3") (pin "4") (pinfunction "1_4") (pintype "passive"))
      (node (ref "X10") (pin "1") (pinfunction "1_1") (pintype "passive"))
    )
    (net (code "56") (name "Net-(RN4B-1)") (class "Default")
      (node (ref "RN4") (pin "1") (pinfunction "1_1") (pintype "passive"))
      (node (ref "RN4") (pin "2") (pinfunction "1_2") (pintype "passive"))
      (node (ref "X10") (pin "4") (pinfunction "1_4") (pintype "passive"))
    )
    (net (code "57") (name "Net-(RN4C-1)") (class "Default")
      (node (ref "RN4") (pin "3") (pinfunction "1_3") (pintype "passive"))
      (node (ref "RN4") (pin "4") (pinfunction "1_4") (pintype "passive"))
      (node (ref "X10") (pin "3") (pinfunction "1_3") (pintype "passive"))
    )
    (net (code "58") (name "OUT0") (class "Default")
      (node (ref "IC2") (pin "15") (pinfunction "(PCINT30/OC2B/ICP)PD6_15") (pintype "bidirectional"))
      (node (ref "IC5") (pin "1") (pinfunction "I1_1") (pintype "input"))
    )
    (net (code "59") (name "OUT1") (class "Default")
      (node (ref "IC2") (pin "16") (pinfunction "(PCINT31/OC2A)PD7_16") (pintype "bidirectional"))
      (node (ref "IC5") (pin "2") (pinfunction "I2_2") (pintype "input"))
    )
    (net (code "60") (name "OUT2") (class "Default")
      (node (ref "IC2") (pin "21") (pinfunction "(PCINT18/TCK)PC2_21") (pintype "output"))
      (node (ref "IC5") (pin "3") (pinfunction "I3_3") (pintype "input"))
    )
    (net (code "61") (name "OUT3") (class "Default")
      (node (ref "IC2") (pin "22") (pinfunction "(PCINT19/TMS)PC3_22") (pintype "output"))
      (node (ref "IC5") (pin "4") (pinfunction "I4_4") (pintype "input"))
    )
    (net (code "62") (name "OUT4") (class "Default")
      (node (ref "IC2") (pin "23") (pinfunction "(PCINT20/TDO)PC4_23") (pintype "output"))
      (node (ref "IC5") (pin "5") (pinfunction "I5_5") (pintype "input"))
    )
    (net (code "63") (name "OUT5") (class "Default")
      (node (ref "IC2") (pin "24") (pinfunction "(PCINT21/TDI)PC5_24") (pintype "output"))
      (node (ref "IC5") (pin "6") (pinfunction "I6_6") (pintype "input"))
    )
    (net (code "64") (name "OUT6") (class "Default")
      (node (ref "IC2") (pin "25") (pinfunction "(PCINT22/TOSC1)PC6_25") (pintype "output"))
      (node (ref "IC5") (pin "7") (pinfunction "I7_7") (pintype "input"))
    )
    (net (code "65") (name "OUT7") (class "Default")
      (node (ref "IC2") (pin "26") (pinfunction "(PCINT23/TOSC2)PC7_26") (pintype "output"))
      (node (ref "IC5") (pin "8") (pinfunction "I8_8") (pintype "input"))
    )
    (net (code "66") (name "RELAIS_0") (class "Default")
      (node (ref "IC5") (pin "18") (pinfunction "O1_18") (pintype "open_collector"))
      (node (ref "K1") (pin "A1") (pinfunction "P$1_A1") (pintype "passive"))
    )
    (net (code "67") (name "RELAIS_1") (class "Default")
      (node (ref "IC5") (pin "17") (pinfunction "O2_17") (pintype "open_collector"))
      (node (ref "K2") (pin "A1") (pinfunction "P$1_A1") (pintype "passive"))
    )
    (net (code "68") (name "RELAIS_2") (class "Default")
      (node (ref "IC5") (pin "16") (pinfunction "O3_16") (pintype "open_collector"))
      (node (ref "K3") (pin "A1") (pinfunction "P$1_A1") (pintype "passive"))
    )
    (net (code "69") (name "RELAIS_3") (class "Default")
      (node (ref "IC5") (pin "15") (pinfunction "O4_15") (pintype "open_collector"))
      (node (ref "K4") (pin "A1") (pinfunction "P$1_A1") (pintype "passive"))
    )
    (net (code "70") (name "RELAIS_4") (class "Default")
      (node (ref "IC5") (pin "14") (pinfunction "O5_14") (pintype "open_collector"))
      (node (ref "K5") (pin "A1") (pinfunction "P$1_A1") (pintype "passive"))
    )
    (net (code "71") (name "RELAIS_5") (class "Default")
      (node (ref "IC5") (pin "13") (pinfunction "O6_13") (pintype "open_collector"))
      (node (ref "K6") (pin "A1") (pinfunction "P$1_A1") (pintype "passive"))
    )
    (net (code "72") (name "RELAIS_6") (class "Default")
      (node (ref "IC5") (pin "12") (pinfunction "O7_12") (pintype "open_collector"))
      (node (ref "K7") (pin "A1") (pinfunction "P$1_A1") (pintype "passive"))
    )
    (net (code "73") (name "RELAIS_7") (class "Default")
      (node (ref "IC5") (pin "11") (pinfunction "O8_11") (pintype "open_collector"))
      (node (ref "K8") (pin "A1") (pinfunction "P$1_A1") (pintype "passive"))
    )
    (net (code "74") (name "RST") (class "Default")
      (node (ref "IC2") (pin "4") (pinfunction "RESET_4") (pintype "input"))
      (node (ref "ISP") (pin "RST") (pinfunction "RST_RST") (pintype "passive"))
      (node (ref "JP1") (pin "2") (pinfunction "2_2") (pintype "passive"))
      (node (ref "R1") (pin "1") (pinfunction "1_1") (pintype "passive"))
    )
    (net (code "75") (name "RXCAN") (class "Default")
      (node (ref "IC3") (pin "2") (pinfunction "RXCAN_2") (pintype "input"))
      (node (ref "IC4") (pin "4") (pinfunction "RXD_4") (pintype "output"))
    )
    (net (code "76") (name "SCK") (class "Default")
      (node (ref "IC2") (pin "3") (pinfunction "(PCINT15/SCK)PB7_3") (pintype "bidirectional"))
      (node (ref "IC3") (pin "13") (pinfunction "SCK_13") (pintype "input"))
      (node (ref "ISP") (pin "SCK") (pinfunction "SCK_SCK") (pintype "passive"))
    )
    (net (code "77") (name "SCL") (class "Default")
      (node (ref "IC2") (pin "19") (pinfunction "(PCINT16/SCL)PC0_19") (pintype "output"))
      (node (ref "RN5") (pin "2") (pinfunction "1_2") (pintype "passive"))
      (node (ref "SCL") (pin "MP") (pinfunction "MP_MP") (pintype "passive"))
    )
    (net (code "78") (name "SDA") (class "Default")
      (node (ref "IC2") (pin "20") (pinfunction "(PCINT17/SDA)PC1_20") (pintype "output"))
      (node (ref "RN5") (pin "1") (pinfunction "1_1") (pintype "passive"))
      (node (ref "SDA") (pin "MP") (pinfunction "MP_MP") (pintype "passive"))
    )
    (net (code "79") (name "TXCAN") (class "Default")
      (node (ref "IC3") (pin "1") (pinfunction "TXCAN_1") (pintype "output"))
      (node (ref "IC4") (pin "1") (pinfunction "TXD_1") (pintype "input"))
    )
    (net (code "80") (name "unconnected-(IC2-(PCINT9{slash}CLKO{slash}T1)PB1-Pad41)") (class "Default")
      (node (ref "IC2") (pin "41") (pinfunction "(PCINT9/CLKO/T1)PB1_41") (pintype "bidirectional"))
    )
    (net (code "81") (name "unconnected-(IC2-(PCINT10{slash}INT2{slash}AIN0)PB2-Pad42)") (class "Default")
      (node (ref "IC2") (pin "42") (pinfunction "(PCINT10/INT2/AIN0)PB2_42") (pintype "bidirectional"))
    )
    (net (code "82") (name "unconnected-(IC2-(PCINT11{slash}OC0A{slash}AIN1)PB3-Pad43)") (class "Default")
      (node (ref "IC2") (pin "43") (pinfunction "(PCINT11/OC0A/AIN1)PB3_43") (pintype "bidirectional"))
    )
    (net (code "83") (name "unconnected-(IC2-(PCINT24{slash}RXD0)PD0-Pad9)") (class "Default")
      (node (ref "IC2") (pin "9") (pinfunction "(PCINT24/RXD0)PD0_9") (pintype "bidirectional"))
    )
    (net (code "84") (name "unconnected-(IC2-(PCINT25{slash}TXD0)PD1-Pad10)") (class "Default")
      (node (ref "IC2") (pin "10") (pinfunction "(PCINT25/TXD0)PD1_10") (pintype "bidirectional"))
    )
    (net (code "85") (name "unconnected-(IC2-(PCINT27{slash}INT1)PD3-Pad12)") (class "Default")
      (node (ref "IC2") (pin "12") (pinfunction "(PCINT27/INT1)PD3_12") (pintype "bidirectional"))
    )
    (net (code "86") (name "unconnected-(IC2-(PCINT28{slash}OC1B)PD4-Pad13)") (class "Default")
      (node (ref "IC2") (pin "13") (pinfunction "(PCINT28/OC1B)PD4_13") (pintype "bidirectional"))
    )
    (net (code "87") (name "unconnected-(IC2-AREF-Pad29)") (class "Default")
      (node (ref "IC2") (pin "29") (pinfunction "AREF_29") (pintype "passive"))
    )
    (net (code "88") (name "unconnected-(IC3-CLKOUT-Pad3)") (class "Default")
      (node (ref "IC3") (pin "3") (pinfunction "CLKOUT_3") (pintype "output"))
    )
    (net (code "89") (name "unconnected-(IC3-RX0BF-Pad11)") (class "Default")
      (node (ref "IC3") (pin "11") (pinfunction "RX0BF_11") (pintype "output"))
    )
    (net (code "90") (name "unconnected-(IC3-RX1BF-Pad10)") (class "Default")
      (node (ref "IC3") (pin "10") (pinfunction "RX1BF_10") (pintype "output"))
    )
    (net (code "91") (name "unconnected-(IC3-TX0RTS-Pad4)") (class "Default")
      (node (ref "IC3") (pin "4") (pinfunction "TX0RTS_4") (pintype "input"))
    )
    (net (code "92") (name "unconnected-(IC3-TX1RTS-Pad5)") (class "Default")
      (node (ref "IC3") (pin "5") (pinfunction "TX1RTS_5") (pintype "input"))
    )
    (net (code "93") (name "unconnected-(IC3-TX2RTS-Pad6)") (class "Default")
      (node (ref "IC3") (pin "6") (pinfunction "TX2RTS_6") (pintype "input"))
    )
    (net (code "94") (name "unconnected-(RN5C-1-Pad3)") (class "Default")
      (node (ref "RN5") (pin "3") (pinfunction "1_3") (pintype "passive"))
    )
  )
)
